# RC_Car_new.net
KiCad netlist of a schematic drawn in EAGLE
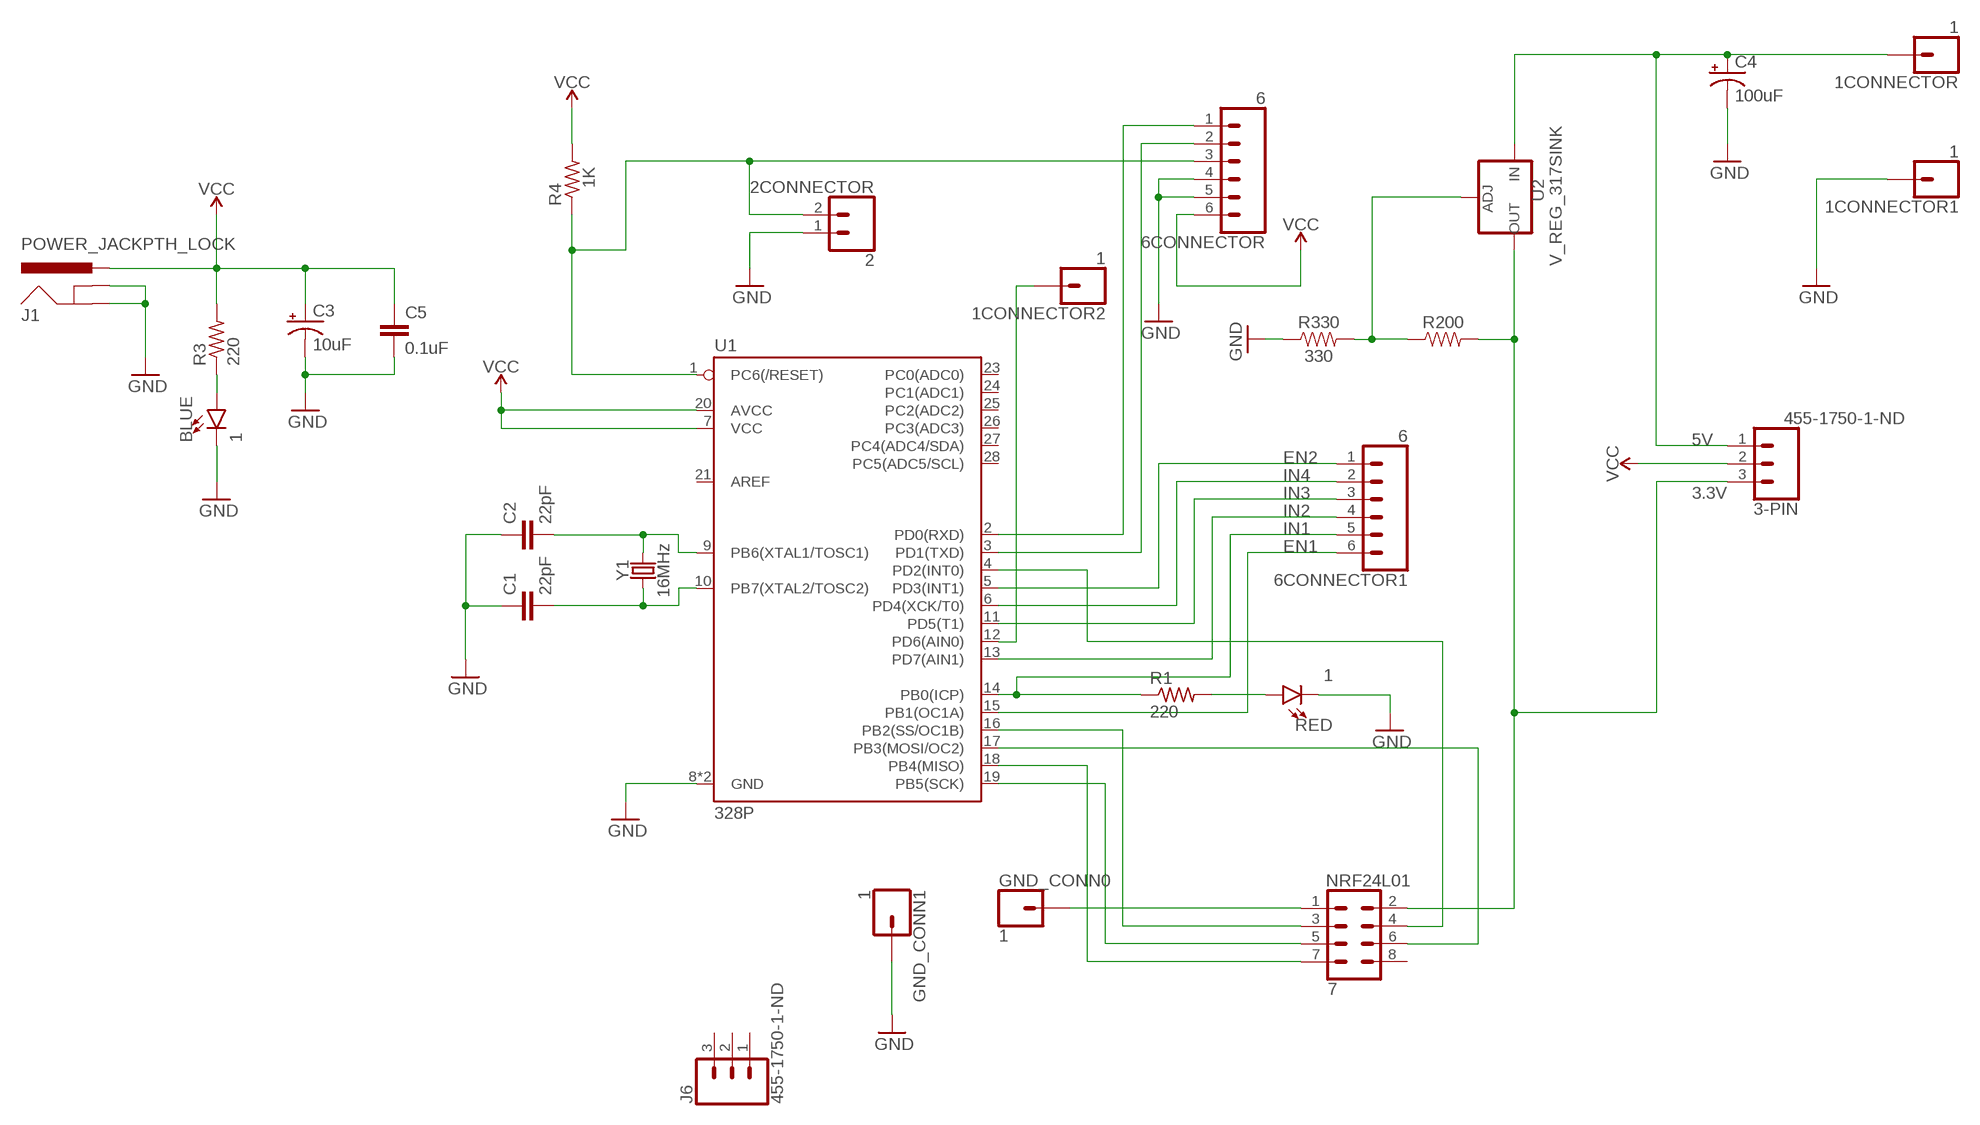
[diagram p0: schematic, sheet 1]

(export (version "E")
  (design (tool "Eeschema 10.0.6"))
  (components
    (comp (ref "1CONNECTOR")
      (value "1")
      (footprint "eagle-import:1X01")
      (libsource (lib "eagle-import") (part "CONN_01"))
    )
    (comp (ref "1CONNECTOR1")
      (value "1")
      (footprint "eagle-import:1X01")
      (libsource (lib "eagle-import") (part "CONN_01"))
    )
    (comp (ref "1CONNECTOR2")
      (value "1")
      (footprint "eagle-import:1X01")
      (libsource (lib "eagle-import") (part "CONN_01"))
    )
    (comp (ref "2CONNECTOR")
      (value "2")
      (footprint "eagle-import:1X02")
      (libsource (lib "eagle-import") (part "CONN_02"))
    )
    (comp (ref "3-PIN")
      (value "455-1750-1-ND")
      (footprint "eagle-import:1X03")
      (libsource (lib "eagle-import") (part "CONN_03"))
    )
    (comp (ref "6CONNECTOR")
      (value "6")
      (footprint "eagle-import:1X06")
      (libsource (lib "eagle-import") (part "CONN_06SILK_FEMALE_PTH"))
    )
    (comp (ref "6CONNECTOR1")
      (value "6")
      (footprint "eagle-import:1X06")
      (libsource (lib "eagle-import") (part "CONN_06SILK_FEMALE_PTH"))
    )
    (comp (ref "BLUE")
      (value "1")
      (footprint "eagle-import:LED_3MM")
      (libsource (lib "eagle-import") (part "LED3MM"))
    )
    (comp (ref "C1")
      (value "22pF")
      (footprint "eagle-import:CAP-PTH-2.54")
      (libsource (lib "eagle-import") (part "22PF-PTH-2.54MM-200V-5%"))
    )
    (comp (ref "C2")
      (value "22pF")
      (footprint "eagle-import:CAP-PTH-2.54")
      (libsource (lib "eagle-import") (part "22PF-PTH-2.54MM-200V-5%"))
    )
    (comp (ref "C3")
      (value "10uF")
      (footprint "eagle-import:CPOL-RADIAL-2.5MM-5MM")
      (libsource (lib "eagle-import") (part "10UF-POLAR-RADIAL-2.5MM-25V-20%"))
    )
    (comp (ref "C4")
      (value "100uF")
      (footprint "eagle-import:CPOL-RADIAL-2.5MM-6.5MM")
      (libsource (lib "eagle-import") (part "100UF-POLAR-RADIAL-2.5MM-25V-20%"))
    )
    (comp (ref "C5")
      (value "0.1uF")
      (footprint "eagle-import:CAP-PTH-SMALL-KIT")
      (libsource (lib "eagle-import") (part "0.1UF-KIT-EZ-50V-20%"))
    )
    (comp (ref "GND_CONN0")
      (value "1")
      (footprint "eagle-import:1X01")
      (libsource (lib "eagle-import") (part "CONN_01"))
    )
    (comp (ref "GND_CONN1")
      (value "1")
      (footprint "eagle-import:1X01")
      (libsource (lib "eagle-import") (part "CONN_01"))
    )
    (comp (ref "J1")
      (value "POWER_JACKPTH_LOCK")
      (footprint "eagle-import:POWER_JACK_PTH_LOCK")
      (libsource (lib "eagle-import") (part "POWER_JACKPTH_LOCK"))
    )
    (comp (ref "J6")
      (value "455-1750-1-ND")
      (footprint "eagle-import:1X03")
      (libsource (lib "eagle-import") (part "CONN_03"))
    )
    (comp (ref "NRF24L01")
      (value "7")
      (footprint "eagle-import:2X4")
      (libsource (lib "eagle-import") (part "CONN_04X2"))
    )
    (comp (ref "R1")
      (value "220")
      (footprint "eagle-import:0207_10")
      (libsource (lib "eagle-import") (part "R-US_0207/10"))
    )
    (comp (ref "R3")
      (value "220")
      (footprint "eagle-import:0207_10")
      (libsource (lib "eagle-import") (part "R-US_0207/10"))
    )
    (comp (ref "R4")
      (value "1K")
      (footprint "eagle-import:0207_10")
      (libsource (lib "eagle-import") (part "R-US_0207/10"))
    )
    (comp (ref "R200")
      (value "RESISTORAXIAL-0.3")
      (footprint "eagle-import:AXIAL-0.3")
      (fields (field (name "PROD_ID") "200"))
      (libsource (lib "eagle-import") (part "RESISTORAXIAL-0.3"))
    )
    (comp (ref "R330")
      (value "330")
      (footprint "eagle-import:AXIAL-0.3")
      (libsource (lib "eagle-import") (part "330OHM-HORIZ-1/10W-5%"))
    )
    (comp (ref "RED")
      (value "1")
      (footprint "eagle-import:LED_3MM")
      (libsource (lib "eagle-import") (part "LED3MM"))
    )
    (comp (ref "U1")
      (value "328P")
      (footprint "eagle-import:DIP28")
      (libsource (lib "eagle-import") (part "ATMEGA328P_PDIP"))
    )
    (comp (ref "U2")
      (value "V_REG_317SINK")
      (footprint "eagle-import:TO220-ADJ")
      (libsource (lib "eagle-import") (part "V_REG_317SINK"))
    )
    (comp (ref "Y1")
      (value "16MHz")
      (footprint "eagle-import:HC49US")
      (libsource (lib "eagle-import") (part "CRYSTAL-16MHZPTH-HC49US"))
    )
  )
  (nets
    (net (code "1") (name "/3.3V") (class "Default")
      (node (ref "3-PIN") (pin "3") (pinfunction "3_3") (pintype "passive"))
      (node (ref "NRF24L01") (pin "2") (pinfunction "2_2") (pintype "passive"))
      (node (ref "R200") (pin "P$2") (pinfunction "2_P$2") (pintype "passive"))
      (node (ref "U2") (pin "OUT") (pinfunction "OUT_OUT") (pintype "output"))
    )
    (net (code "2") (name "/5V") (class "Default")
      (node (ref "1CONNECTOR") (pin "1") (pinfunction "1_1") (pintype "passive"))
      (node (ref "3-PIN") (pin "1") (pinfunction "1_1") (pintype "passive"))
      (node (ref "C4") (pin "1") (pinfunction "+_1") (pintype "passive"))
      (node (ref "U2") (pin "IN") (pinfunction "IN_IN") (pintype "input"))
    )
    (net (code "3") (name "/EN1") (class "Default")
      (node (ref "6CONNECTOR1") (pin "6") (pinfunction "6_6") (pintype "passive"))
      (node (ref "U1") (pin "15") (pinfunction "PB1(OC1A)_15") (pintype "bidirectional"))
    )
    (net (code "4") (name "/EN2") (class "Default")
      (node (ref "6CONNECTOR1") (pin "1") (pinfunction "1_1") (pintype "passive"))
      (node (ref "U1") (pin "5") (pinfunction "PD3(INT1)_5") (pintype "bidirectional"))
    )
    (net (code "5") (name "/IN1") (class "Default")
      (node (ref "6CONNECTOR1") (pin "5") (pinfunction "5_5") (pintype "passive"))
      (node (ref "R1") (pin "1") (pinfunction "1_1") (pintype "passive"))
      (node (ref "U1") (pin "14") (pinfunction "PB0(ICP)_14") (pintype "bidirectional"))
    )
    (net (code "6") (name "/IN2") (class "Default")
      (node (ref "6CONNECTOR1") (pin "4") (pinfunction "4_4") (pintype "passive"))
      (node (ref "U1") (pin "13") (pinfunction "PD7(AIN1)_13") (pintype "bidirectional"))
    )
    (net (code "7") (name "/IN3") (class "Default")
      (node (ref "6CONNECTOR1") (pin "3") (pinfunction "3_3") (pintype "passive"))
      (node (ref "U1") (pin "11") (pinfunction "PD5(T1)_11") (pintype "bidirectional"))
    )
    (net (code "8") (name "/IN4") (class "Default")
      (node (ref "6CONNECTOR1") (pin "2") (pinfunction "2_2") (pintype "passive"))
      (node (ref "U1") (pin "6") (pinfunction "PD4(XCK/T0)_6") (pintype "bidirectional"))
    )
    (net (code "9") (name "GND") (class "Default")
      (node (ref "1CONNECTOR1") (pin "1") (pinfunction "1_1") (pintype "passive"))
      (node (ref "2CONNECTOR") (pin "1") (pinfunction "1_1") (pintype "passive"))
      (node (ref "6CONNECTOR") (pin "4") (pinfunction "4_4") (pintype "passive"))
      (node (ref "6CONNECTOR") (pin "5") (pinfunction "5_5") (pintype "passive"))
      (node (ref "BLUE") (pin "K") (pinfunction "C_K") (pintype "passive"))
      (node (ref "C1") (pin "1") (pinfunction "1_1") (pintype "passive"))
      (node (ref "C2") (pin "1") (pinfunction "1_1") (pintype "passive"))
      (node (ref "C3") (pin "2") (pinfunction "-_2") (pintype "passive"))
      (node (ref "C4") (pin "2") (pinfunction "-_2") (pintype "passive"))
      (node (ref "C5") (pin "2") (pinfunction "2_2") (pintype "passive"))
      (node (ref "GND_CONN1") (pin "1") (pinfunction "1_1") (pintype "passive"))
      (node (ref "J1") (pin "GND") (pinfunction "GND_GND") (pintype "bidirectional"))
      (node (ref "J1") (pin "GNDBREAK") (pinfunction "GNDBREAK_GNDBREAK") (pintype "bidirectional"))
      (node (ref "R330") (pin "P$1") (pinfunction "1_P$1") (pintype "passive"))
      (node (ref "RED") (pin "K") (pinfunction "C_K") (pintype "passive"))
      (node (ref "U1") (pin "22") (pinfunction "GND_22") (pintype "bidirectional"))
      (node (ref "U1") (pin "8") (pinfunction "GND_8") (pintype "bidirectional"))
    )
    (net (code "10") (name "Net-(BLUE-PadA)") (class "Default")
      (node (ref "BLUE") (pin "A") (pinfunction "A_A") (pintype "passive"))
      (node (ref "R3") (pin "1") (pinfunction "1_1") (pintype "passive"))
    )
    (net (code "11") (name "Net-(GND_CONN0-Pad1)") (class "Default")
      (node (ref "GND_CONN0") (pin "1") (pinfunction "1_1") (pintype "passive"))
      (node (ref "NRF24L01") (pin "1") (pinfunction "1_1") (pintype "passive"))
    )
    (net (code "12") (name "Net-(R1-Pad2)") (class "Default")
      (node (ref "R1") (pin "2") (pinfunction "2_2") (pintype "passive"))
      (node (ref "RED") (pin "A") (pinfunction "A_A") (pintype "passive"))
    )
    (net (code "13") (name "Net-(R200-1)") (class "Default")
      (node (ref "R200") (pin "P$1") (pinfunction "1_P$1") (pintype "passive"))
      (node (ref "R330") (pin "P$2") (pinfunction "2_P$2") (pintype "passive"))
      (node (ref "U2") (pin "ADJ") (pinfunction "ADJ_ADJ") (pintype "input"))
    )
    (net (code "14") (name "Net-(U1-PB2(SS{slash}OC1B))") (class "Default")
      (node (ref "NRF24L01") (pin "3") (pinfunction "3_3") (pintype "passive"))
      (node (ref "U1") (pin "16") (pinfunction "PB2(SS/OC1B)_16") (pintype "bidirectional"))
    )
    (net (code "15") (name "Net-(U1-PB3(MOSI{slash}OC2))") (class "Default")
      (node (ref "NRF24L01") (pin "6") (pinfunction "6_6") (pintype "passive"))
      (node (ref "U1") (pin "17") (pinfunction "PB3(MOSI/OC2)_17") (pintype "bidirectional"))
    )
    (net (code "16") (name "Net-(U1-PB4(MISO))") (class "Default")
      (node (ref "NRF24L01") (pin "7") (pinfunction "7_7") (pintype "passive"))
      (node (ref "U1") (pin "18") (pinfunction "PB4(MISO)_18") (pintype "bidirectional"))
    )
    (net (code "17") (name "Net-(U1-PB5(SCK))") (class "Default")
      (node (ref "NRF24L01") (pin "5") (pinfunction "5_5") (pintype "passive"))
      (node (ref "U1") (pin "19") (pinfunction "PB5(SCK)_19") (pintype "bidirectional"))
    )
    (net (code "18") (name "Net-(U1-PB6(XTAL1{slash}TOSC1))") (class "Default")
      (node (ref "C2") (pin "2") (pinfunction "2_2") (pintype "passive"))
      (node (ref "U1") (pin "9") (pinfunction "PB6(XTAL1/TOSC1)_9") (pintype "bidirectional"))
      (node (ref "Y1") (pin "2") (pinfunction "2_2") (pintype "passive"))
    )
    (net (code "19") (name "Net-(U1-PB7(XTAL2{slash}TOSC2))") (class "Default")
      (node (ref "C1") (pin "2") (pinfunction "2_2") (pintype "passive"))
      (node (ref "U1") (pin "10") (pinfunction "PB7(XTAL2/TOSC2)_10") (pintype "bidirectional"))
      (node (ref "Y1") (pin "1") (pinfunction "1_1") (pintype "passive"))
    )
    (net (code "20") (name "Net-(U1-PC6({slash}RESET))") (class "Default")
      (node (ref "2CONNECTOR") (pin "2") (pinfunction "2_2") (pintype "passive"))
      (node (ref "6CONNECTOR") (pin "3") (pinfunction "3_3") (pintype "passive"))
      (node (ref "R4") (pin "1") (pinfunction "1_1") (pintype "passive"))
      (node (ref "U1") (pin "1") (pinfunction "PC6(/RESET)_1") (pintype "bidirectional"))
    )
    (net (code "21") (name "Net-(U1-PD0(RXD))") (class "Default")
      (node (ref "6CONNECTOR") (pin "1") (pinfunction "1_1") (pintype "passive"))
      (node (ref "U1") (pin "2") (pinfunction "PD0(RXD)_2") (pintype "bidirectional"))
    )
    (net (code "22") (name "Net-(U1-PD1(TXD))") (class "Default")
      (node (ref "6CONNECTOR") (pin "2") (pinfunction "2_2") (pintype "passive"))
      (node (ref "U1") (pin "3") (pinfunction "PD1(TXD)_3") (pintype "bidirectional"))
    )
    (net (code "23") (name "Net-(U1-PD2(INT0))") (class "Default")
      (node (ref "NRF24L01") (pin "4") (pinfunction "4_4") (pintype "passive"))
      (node (ref "U1") (pin "4") (pinfunction "PD2(INT0)_4") (pintype "bidirectional"))
    )
    (net (code "24") (name "Net-(U1-PD6(AIN0))") (class "Default")
      (node (ref "1CONNECTOR2") (pin "1") (pinfunction "1_1") (pintype "passive"))
      (node (ref "U1") (pin "12") (pinfunction "PD6(AIN0)_12") (pintype "bidirectional"))
    )
    (net (code "25") (name "VCC") (class "Default")
      (node (ref "3-PIN") (pin "2") (pinfunction "2_2") (pintype "passive"))
      (node (ref "6CONNECTOR") (pin "6") (pinfunction "6_6") (pintype "passive"))
      (node (ref "C3") (pin "1") (pinfunction "+_1") (pintype "passive"))
      (node (ref "C5") (pin "1") (pinfunction "1_1") (pintype "passive"))
      (node (ref "J1") (pin "PWR") (pinfunction "PWR_PWR") (pintype "bidirectional"))
      (node (ref "R3") (pin "2") (pinfunction "2_2") (pintype "passive"))
      (node (ref "R4") (pin "2") (pinfunction "2_2") (pintype "passive"))
      (node (ref "U1") (pin "20") (pinfunction "AVCC_20") (pintype "bidirectional"))
      (node (ref "U1") (pin "7") (pinfunction "VCC_7") (pintype "bidirectional"))
    )
    (net (code "26") (name "unconnected-(J6-Pad1)") (class "Default")
      (node (ref "J6") (pin "1") (pinfunction "1_1") (pintype "passive"))
    )
    (net (code "27") (name "unconnected-(J6-Pad2)") (class "Default")
      (node (ref "J6") (pin "2") (pinfunction "2_2") (pintype "passive"))
    )
    (net (code "28") (name "unconnected-(J6-Pad3)") (class "Default")
      (node (ref "J6") (pin "3") (pinfunction "3_3") (pintype "passive"))
    )
    (net (code "29") (name "unconnected-(NRF24L01-Pad8)") (class "Default")
      (node (ref "NRF24L01") (pin "8") (pinfunction "8_8") (pintype "passive"))
    )
    (net (code "30") (name "unconnected-(U1-AREF-Pad21)") (class "Default")
      (node (ref "U1") (pin "21") (pinfunction "AREF_21") (pintype "bidirectional"))
    )
    (net (code "31") (name "unconnected-(U1-PC0(ADC0)-Pad23)") (class "Default")
      (node (ref "U1") (pin "23") (pinfunction "PC0(ADC0)_23") (pintype "bidirectional"))
    )
    (net (code "32") (name "unconnected-(U1-PC1(ADC1)-Pad24)") (class "Default")
      (node (ref "U1") (pin "24") (pinfunction "PC1(ADC1)_24") (pintype "bidirectional"))
    )
    (net (code "33") (name "unconnected-(U1-PC2(ADC2)-Pad25)") (class "Default")
      (node (ref "U1") (pin "25") (pinfunction "PC2(ADC2)_25") (pintype "bidirectional"))
    )
    (net (code "34") (name "unconnected-(U1-PC3(ADC3)-Pad26)") (class "Default")
      (node (ref "U1") (pin "26") (pinfunction "PC3(ADC3)_26") (pintype "bidirectional"))
    )
    (net (code "35") (name "unconnected-(U1-PC4(ADC4{slash}SDA)-Pad27)") (class "Default")
      (node (ref "U1") (pin "27") (pinfunction "PC4(ADC4/SDA)_27") (pintype "bidirectional"))
    )
    (net (code "36") (name "unconnected-(U1-PC5(ADC5{slash}SCL)-Pad28)") (class "Default")
      (node (ref "U1") (pin "28") (pinfunction "PC5(ADC5/SCL)_28") (pintype "bidirectional"))
    )
  )
)
